# r0_4_0.net
KiCad netlist of a schematic drawn in EAGLE
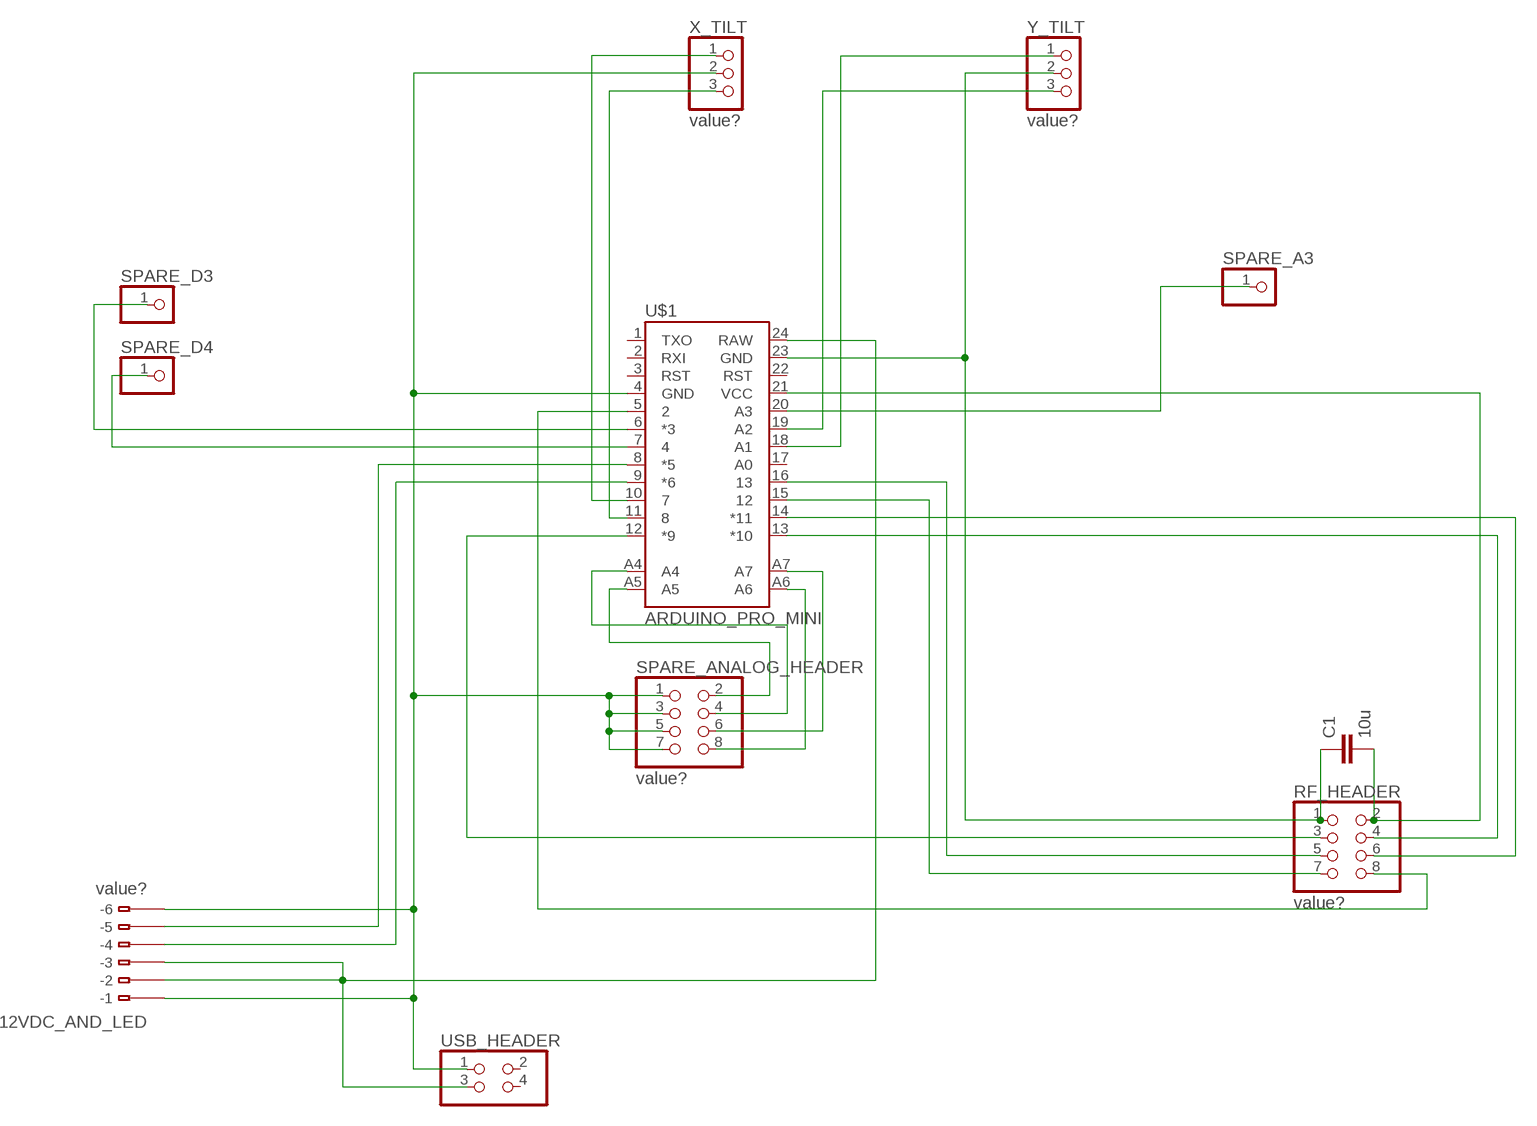
[diagram p0: schematic, sheet 1]

(export (version "E")
  (design (tool "Eeschema 10.0.6"))
  (components
    (comp (ref "12VDC_AND_LED")
      (value "value?")
      (footprint "eagle-import:234-206")
      (fields (field (name "MPN") "234-206"))
      (libsource (lib "eagle-import") (part "234-206"))
    )
    (comp (ref "C1")
      (value "10u")
      (footprint "eagle-import:CAP-PTH-SMALL")
      (libsource (lib "eagle-import") (part "CAPPTH"))
    )
    (comp (ref "RF_HEADER")
      (value "value?")
      (footprint "eagle-import:2X04")
      (libsource (lib "eagle-import") (part "PINHD-2X4"))
    )
    (comp (ref "SPARE_A3")
      (value "PINHD-1X1")
      (footprint "eagle-import:1X01")
      (libsource (lib "eagle-import") (part "PINHD-1X1"))
    )
    (comp (ref "SPARE_ANALOG_HEADER")
      (value "value?")
      (footprint "eagle-import:2X04")
      (libsource (lib "eagle-import") (part "PINHD-2X4"))
    )
    (comp (ref "SPARE_D3")
      (value "PINHD-1X1")
      (footprint "eagle-import:1X01")
      (libsource (lib "eagle-import") (part "PINHD-1X1"))
    )
    (comp (ref "SPARE_D4")
      (value "PINHD-1X1")
      (footprint "eagle-import:1X01")
      (libsource (lib "eagle-import") (part "PINHD-1X1"))
    )
    (comp (ref "U$1")
      (value "ARDUINO_PRO_MINI")
      (footprint "eagle-import:ARDUINO_PRO_MINI")
      (libsource (lib "eagle-import") (part "ARDUINO_PRO_MINI"))
    )
    (comp (ref "USB_HEADER")
      (value "PINHD-2X2")
      (footprint "eagle-import:2X02")
      (libsource (lib "eagle-import") (part "PINHD-2X2"))
    )
    (comp (ref "X_TILT")
      (value "value?")
      (footprint "eagle-import:1X03")
      (libsource (lib "eagle-import") (part "PINHD-1X3"))
    )
    (comp (ref "Y_TILT")
      (value "value?")
      (footprint "eagle-import:1X03")
      (libsource (lib "eagle-import") (part "PINHD-1X3"))
    )
  )
  (nets
    (net (code "1") (name "Net-(12VDC_AND_LED-B-1)") (class "Default")
      (node (ref "12VDC_AND_LED") (pin "B1") (pinfunction "B-1_B1") (pintype "passive"))
      (node (ref "12VDC_AND_LED") (pin "B6") (pinfunction "B-6_B6") (pintype "passive"))
      (node (ref "SPARE_ANALOG_HEADER") (pin "1") (pinfunction "1_1") (pintype "passive"))
      (node (ref "SPARE_ANALOG_HEADER") (pin "3") (pinfunction "3_3") (pintype "passive"))
      (node (ref "SPARE_ANALOG_HEADER") (pin "5") (pinfunction "5_5") (pintype "passive"))
      (node (ref "SPARE_ANALOG_HEADER") (pin "7") (pinfunction "7_7") (pintype "passive"))
      (node (ref "U$1") (pin "4") (pinfunction "GND_4") (pintype "bidirectional"))
      (node (ref "USB_HEADER") (pin "1") (pinfunction "1_1") (pintype "passive"))
      (node (ref "X_TILT") (pin "2") (pinfunction "2_2") (pintype "passive"))
    )
    (net (code "2") (name "Net-(12VDC_AND_LED-B-2)") (class "Default")
      (node (ref "12VDC_AND_LED") (pin "B2") (pinfunction "B-2_B2") (pintype "passive"))
      (node (ref "12VDC_AND_LED") (pin "B3") (pinfunction "B-3_B3") (pintype "passive"))
      (node (ref "U$1") (pin "24") (pinfunction "RAW_24") (pintype "bidirectional"))
      (node (ref "USB_HEADER") (pin "3") (pinfunction "3_3") (pintype "passive"))
    )
    (net (code "3") (name "Net-(12VDC_AND_LED-B-4)") (class "Default")
      (node (ref "12VDC_AND_LED") (pin "B4") (pinfunction "B-4_B4") (pintype "passive"))
      (node (ref "U$1") (pin "9") (pinfunction "*6_9") (pintype "bidirectional"))
    )
    (net (code "4") (name "Net-(12VDC_AND_LED-B-5)") (class "Default")
      (node (ref "12VDC_AND_LED") (pin "B5") (pinfunction "B-5_B5") (pintype "passive"))
      (node (ref "U$1") (pin "8") (pinfunction "*5_8") (pintype "bidirectional"))
    )
    (net (code "5") (name "Net-(C1-Pad1)") (class "Default")
      (node (ref "C1") (pin "1") (pinfunction "1_1") (pintype "passive"))
      (node (ref "RF_HEADER") (pin "1") (pinfunction "1_1") (pintype "passive"))
      (node (ref "U$1") (pin "23") (pinfunction "GND_23") (pintype "bidirectional"))
      (node (ref "Y_TILT") (pin "2") (pinfunction "2_2") (pintype "passive"))
    )
    (net (code "6") (name "Net-(SPARE_ANALOG_HEADER-Pad2)") (class "Default")
      (node (ref "SPARE_ANALOG_HEADER") (pin "2") (pinfunction "2_2") (pintype "passive"))
      (node (ref "U$1") (pin "A5") (pinfunction "A5_A5") (pintype "bidirectional"))
    )
    (net (code "7") (name "Net-(SPARE_ANALOG_HEADER-Pad4)") (class "Default")
      (node (ref "SPARE_ANALOG_HEADER") (pin "4") (pinfunction "4_4") (pintype "passive"))
      (node (ref "U$1") (pin "A4") (pinfunction "A4_A4") (pintype "bidirectional"))
    )
    (net (code "8") (name "Net-(SPARE_ANALOG_HEADER-Pad6)") (class "Default")
      (node (ref "SPARE_ANALOG_HEADER") (pin "6") (pinfunction "6_6") (pintype "passive"))
      (node (ref "U$1") (pin "A7") (pinfunction "A7_A7") (pintype "bidirectional"))
    )
    (net (code "9") (name "Net-(SPARE_ANALOG_HEADER-Pad8)") (class "Default")
      (node (ref "SPARE_ANALOG_HEADER") (pin "8") (pinfunction "8_8") (pintype "passive"))
      (node (ref "U$1") (pin "A6") (pinfunction "A6_A6") (pintype "bidirectional"))
    )
    (net (code "10") (name "Net-(U$1-*3)") (class "Default")
      (node (ref "SPARE_D3") (pin "1") (pinfunction "1_1") (pintype "passive"))
      (node (ref "U$1") (pin "6") (pinfunction "*3_6") (pintype "bidirectional"))
    )
    (net (code "11") (name "Net-(U$1-*9)") (class "Default")
      (node (ref "RF_HEADER") (pin "3") (pinfunction "3_3") (pintype "passive"))
      (node (ref "U$1") (pin "12") (pinfunction "*9_12") (pintype "bidirectional"))
    )
    (net (code "12") (name "Net-(U$1-*10)") (class "Default")
      (node (ref "RF_HEADER") (pin "4") (pinfunction "4_4") (pintype "passive"))
      (node (ref "U$1") (pin "13") (pinfunction "*10_13") (pintype "bidirectional"))
    )
    (net (code "13") (name "Net-(U$1-*11)") (class "Default")
      (node (ref "RF_HEADER") (pin "6") (pinfunction "6_6") (pintype "passive"))
      (node (ref "U$1") (pin "14") (pinfunction "*11_14") (pintype "bidirectional"))
    )
    (net (code "14") (name "Net-(U$1-2)") (class "Default")
      (node (ref "RF_HEADER") (pin "8") (pinfunction "8_8") (pintype "passive"))
      (node (ref "U$1") (pin "5") (pinfunction "2_5") (pintype "bidirectional"))
    )
    (net (code "15") (name "Net-(U$1-4)") (class "Default")
      (node (ref "SPARE_D4") (pin "1") (pinfunction "1_1") (pintype "passive"))
      (node (ref "U$1") (pin "7") (pinfunction "4_7") (pintype "bidirectional"))
    )
    (net (code "16") (name "Net-(U$1-7)") (class "Default")
      (node (ref "U$1") (pin "10") (pinfunction "7_10") (pintype "bidirectional"))
      (node (ref "X_TILT") (pin "1") (pinfunction "1_1") (pintype "passive"))
    )
    (net (code "17") (name "Net-(U$1-8)") (class "Default")
      (node (ref "U$1") (pin "11") (pinfunction "8_11") (pintype "bidirectional"))
      (node (ref "X_TILT") (pin "3") (pinfunction "3_3") (pintype "passive"))
    )
    (net (code "18") (name "Net-(U$1-12)") (class "Default")
      (node (ref "RF_HEADER") (pin "7") (pinfunction "7_7") (pintype "passive"))
      (node (ref "U$1") (pin "15") (pinfunction "12_15") (pintype "bidirectional"))
    )
    (net (code "19") (name "Net-(U$1-13)") (class "Default")
      (node (ref "RF_HEADER") (pin "5") (pinfunction "5_5") (pintype "passive"))
      (node (ref "U$1") (pin "16") (pinfunction "13_16") (pintype "bidirectional"))
    )
    (net (code "20") (name "Net-(U$1-A1)") (class "Default")
      (node (ref "U$1") (pin "18") (pinfunction "A1_18") (pintype "bidirectional"))
      (node (ref "Y_TILT") (pin "1") (pinfunction "1_1") (pintype "passive"))
    )
    (net (code "21") (name "Net-(U$1-A2)") (class "Default")
      (node (ref "U$1") (pin "19") (pinfunction "A2_19") (pintype "bidirectional"))
      (node (ref "Y_TILT") (pin "3") (pinfunction "3_3") (pintype "passive"))
    )
    (net (code "22") (name "Net-(U$1-A3)") (class "Default")
      (node (ref "SPARE_A3") (pin "1") (pinfunction "1_1") (pintype "passive"))
      (node (ref "U$1") (pin "20") (pinfunction "A3_20") (pintype "bidirectional"))
    )
    (net (code "23") (name "Net-(U$1-VCC)") (class "Default")
      (node (ref "C1") (pin "2") (pinfunction "2_2") (pintype "passive"))
      (node (ref "RF_HEADER") (pin "2") (pinfunction "2_2") (pintype "passive"))
      (node (ref "U$1") (pin "21") (pinfunction "VCC_21") (pintype "bidirectional"))
    )
    (net (code "24") (name "unconnected-(12VDC_AND_LED--1-PadA1)") (class "Default")
      (node (ref "12VDC_AND_LED") (pin "A1") (pinfunction "-1_A1") (pintype "passive"))
    )
    (net (code "25") (name "unconnected-(12VDC_AND_LED--2-PadA2)") (class "Default")
      (node (ref "12VDC_AND_LED") (pin "A2") (pinfunction "-2_A2") (pintype "passive"))
    )
    (net (code "26") (name "unconnected-(12VDC_AND_LED--3-PadA3)") (class "Default")
      (node (ref "12VDC_AND_LED") (pin "A3") (pinfunction "-3_A3") (pintype "passive"))
    )
    (net (code "27") (name "unconnected-(12VDC_AND_LED--4-PadA4)") (class "Default")
      (node (ref "12VDC_AND_LED") (pin "A4") (pinfunction "-4_A4") (pintype "passive"))
    )
    (net (code "28") (name "unconnected-(12VDC_AND_LED--5-PadA5)") (class "Default")
      (node (ref "12VDC_AND_LED") (pin "A5") (pinfunction "-5_A5") (pintype "passive"))
    )
    (net (code "29") (name "unconnected-(12VDC_AND_LED--6-PadA6)") (class "Default")
      (node (ref "12VDC_AND_LED") (pin "A6") (pinfunction "-6_A6") (pintype "passive"))
    )
    (net (code "30") (name "unconnected-(U$1-A0-Pad17)") (class "Default")
      (node (ref "U$1") (pin "17") (pinfunction "A0_17") (pintype "bidirectional"))
    )
    (net (code "31") (name "unconnected-(U$1-RST-Pad3)") (class "Default")
      (node (ref "U$1") (pin "3") (pinfunction "RST_3") (pintype "bidirectional"))
    )
    (net (code "32") (name "unconnected-(U$1-RST-Pad22)") (class "Default")
      (node (ref "U$1") (pin "22") (pinfunction "RST_22") (pintype "bidirectional"))
    )
    (net (code "33") (name "unconnected-(U$1-RXI-Pad2)") (class "Default")
      (node (ref "U$1") (pin "2") (pinfunction "RXI_2") (pintype "bidirectional"))
    )
    (net (code "34") (name "unconnected-(U$1-TXO-Pad1)") (class "Default")
      (node (ref "U$1") (pin "1") (pinfunction "TXO_1") (pintype "bidirectional"))
    )
    (net (code "35") (name "unconnected-(USB_HEADER-Pad2)") (class "Default")
      (node (ref "USB_HEADER") (pin "2") (pinfunction "2_2") (pintype "passive"))
    )
    (net (code "36") (name "unconnected-(USB_HEADER-Pad4)") (class "Default")
      (node (ref "USB_HEADER") (pin "4") (pinfunction "4_4") (pintype "passive"))
    )
  )
)
